# M3_Chip.net
KiCad netlist of a schematic drawn in Altium Designer
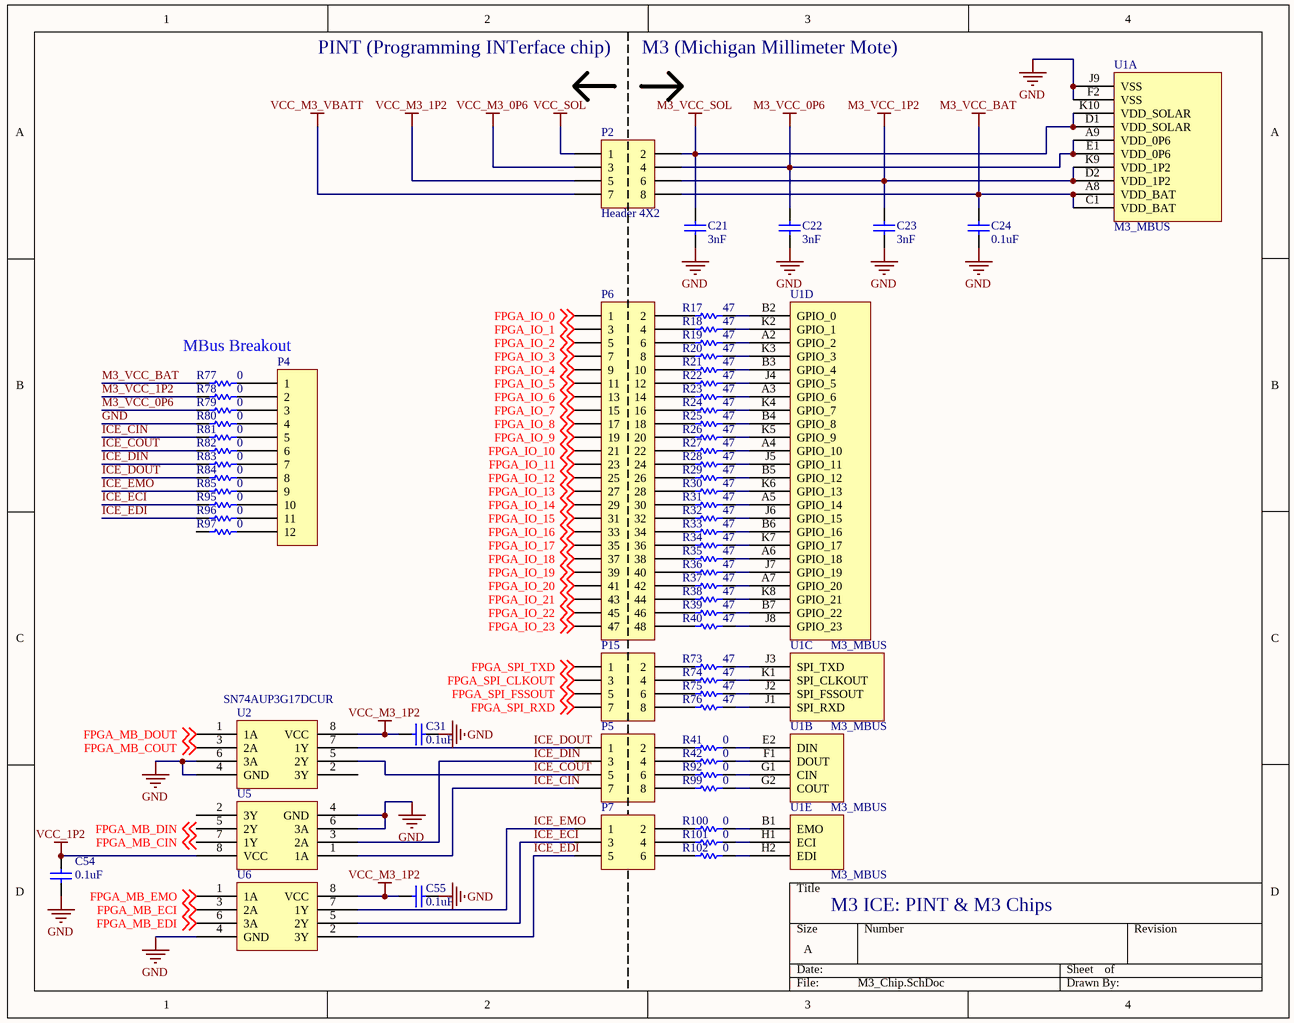
[diagram p0: M3_Chip.SchDoc]

(export (version "E")
  (design (tool "Eeschema 10.0.6"))
  (components
    (comp (ref "C21")
      (value "3nF")
      (footprint "1608[0603]")
      (description "Capacitor (Semiconductor SIM Model)")
      (fields
        (field (name "DISTPARTNO") "399-7893-1-ND")
        (field (name "MANPARTNO") "C0603C302K5GACTU")
        (field (name "PUBLISHER") "Altium Limited")
      )
      (libsource (lib "Miscellaneous Devices") (part "Cap Semi"))
    )
    (comp (ref "C22")
      (value "3nF")
      (footprint "1608[0603]")
      (description "Capacitor (Semiconductor SIM Model)")
      (fields
        (field (name "DISTPARTNO") "399-7893-1-ND")
        (field (name "MANPARTNO") "C0603C302K5GACTU")
        (field (name "PUBLISHER") "Altium Limited")
      )
      (libsource (lib "Miscellaneous Devices") (part "Cap Semi"))
    )
    (comp (ref "C23")
      (value "3nF")
      (footprint "1608[0603]")
      (description "Capacitor (Semiconductor SIM Model)")
      (fields
        (field (name "DISTPARTNO") "399-7893-1-ND")
        (field (name "MANPARTNO") "C0603C302K5GACTU")
        (field (name "PUBLISHER") "Altium Limited")
      )
      (libsource (lib "Miscellaneous Devices") (part "Cap Semi"))
    )
    (comp (ref "C24")
      (value "0.1uF")
      (footprint "1608[0603]")
      (description "Capacitor (Semiconductor SIM Model)")
      (fields
        (field (name "DISTPARTNO") "1276-1005-1-ND")
        (field (name "MANPARTNO") "CL10B104KO8NNNC")
        (field (name "PUBLISHER") "Altium Limited")
      )
      (libsource (lib "Miscellaneous Devices") (part "Cap Semi"))
    )
    (comp (ref "C31")
      (value "0.1uF")
      (footprint "1608[0603]")
      (description "Capacitor (Semiconductor SIM Model)")
      (fields
        (field (name "DISTPARTNO") "1276-1005-1-ND")
        (field (name "MANPARTNO") "CL10B104KO8NNNC")
        (field (name "PUBLISHER") "Altium Limited")
      )
      (libsource (lib "Miscellaneous Devices") (part "Cap Semi"))
    )
    (comp (ref "C54")
      (value "0.1uF")
      (footprint "1608[0603]")
      (description "Capacitor (Semiconductor SIM Model)")
      (fields
        (field (name "DISTPARTNO") "1276-1005-1-ND")
        (field (name "MANPARTNO") "CL10B104KO8NNNC")
        (field (name "PUBLISHER") "Altium Limited")
      )
      (libsource (lib "Miscellaneous Devices") (part "Cap Semi"))
    )
    (comp (ref "C55")
      (value "0.1uF")
      (footprint "1608[0603]")
      (description "Capacitor (Semiconductor SIM Model)")
      (fields
        (field (name "DISTPARTNO") "1276-1005-1-ND")
        (field (name "MANPARTNO") "CL10B104KO8NNNC")
        (field (name "PUBLISHER") "Altium Limited")
      )
      (libsource (lib "Miscellaneous Devices") (part "Cap Semi"))
    )
    (comp (ref "P2")
      (value "Header 4X2")
      (footprint "HDR2X4")
      (description "Header, 4-Pin, Dual row")
      (fields
        (field (name "DISTPARTNO") "A26530-04-ND")
        (field (name "MANPARTNO") "4-103328-0-04")
        (field (name "PUBLISHER") "Altium Limited")
      )
      (libsource (lib "Miscellaneous Connectors") (part "Header 4X2"))
    )
    (comp (ref "P4")
      (value "MBus Breakout")
      (footprint "HDR1X12")
      (description "Header, 12-Pin")
      (fields
        (field (name "DISTPARTNO") "A26514-12-ND")
        (field (name "MANPARTNO") "4-103327-0-12")
        (field (name "PUBLISHER") "Altium Limited")
      )
      (libsource (lib "Miscellaneous Connectors") (part "Header 12"))
    )
    (comp (ref "P5")
      (value "Header 4X2")
      (footprint "HDR2X4")
      (description "Header, 4-Pin, Dual row")
      (fields
        (field (name "MANPARTNO") "4-103328-0-04")
        (field (name "DISTPARTNO") "A26530-04-ND")
        (field (name "PUBLISHER") "Altium Limited")
      )
      (libsource (lib "Miscellaneous Connectors") (part "Header 4X2"))
    )
    (comp (ref "P6")
      (value "Header 24X2")
      (footprint "HDR2X24")
      (description "Header, 24-Pin, Dual row")
      (fields
        (field (name "MANPARTNO") "4-103328-0-24")
        (field (name "DISTPARTNO") "A26530-24-ND")
        (field (name "PUBLISHER") "Altium Limited")
      )
      (libsource (lib "Miscellaneous Connectors") (part "Header 24X2"))
    )
    (comp (ref "P7")
      (value "Header 3X2")
      (footprint "HDR2X3")
      (description "Header, 3-Pin, Dual row")
      (fields
        (field (name "DISTPARTNO") "A26525-03-ND")
        (field (name "MANPARTNO") "4-103777-0-03")
        (field (name "PUBLISHER") "Altium Limited")
      )
      (libsource (lib "Miscellaneous Connectors") (part "Header 3X2"))
    )
    (comp (ref "P15")
      (value "Header 4X2")
      (footprint "HDR2X4")
      (description "Header, 4-Pin, Dual row")
      (fields
        (field (name "MANPARTNO") "4-103328-0-04")
        (field (name "DISTPARTNO") "A26530-04-ND")
        (field (name "PUBLISHER") "Altium Limited")
      )
      (libsource (lib "Miscellaneous Connectors") (part "Header 4X2"))
    )
    (comp (ref "R17")
      (value "47")
      (footprint "0603")
      (description "Semiconductor Resistor")
      (fields
        (field (name "DISTPARTNO") "P47GCT-ND")
        (field (name "MANPARTNO") "ERJ-3GEYJ470V")
        (field (name "PUBLISHER") "Altium Limited")
      )
      (libsource (lib "M3") (part "Res Chip"))
    )
    (comp (ref "R18")
      (value "47")
      (footprint "0603")
      (description "Semiconductor Resistor")
      (fields
        (field (name "DISTPARTNO") "P47GCT-ND")
        (field (name "MANPARTNO") "ERJ-3GEYJ470V")
        (field (name "PUBLISHER") "Altium Limited")
      )
      (libsource (lib "M3") (part "Res Chip"))
    )
    (comp (ref "R19")
      (value "47")
      (footprint "0603")
      (description "Semiconductor Resistor")
      (fields
        (field (name "DISTPARTNO") "P47GCT-ND")
        (field (name "MANPARTNO") "ERJ-3GEYJ470V")
        (field (name "PUBLISHER") "Altium Limited")
      )
      (libsource (lib "M3") (part "Res Chip"))
    )
    (comp (ref "R20")
      (value "47")
      (footprint "0603")
      (description "Semiconductor Resistor")
      (fields
        (field (name "DISTPARTNO") "P47GCT-ND")
        (field (name "MANPARTNO") "ERJ-3GEYJ470V")
        (field (name "PUBLISHER") "Altium Limited")
      )
      (libsource (lib "M3") (part "Res Chip"))
    )
    (comp (ref "R21")
      (value "47")
      (footprint "0603")
      (description "Semiconductor Resistor")
      (fields
        (field (name "DISTPARTNO") "P47GCT-ND")
        (field (name "MANPARTNO") "ERJ-3GEYJ470V")
        (field (name "PUBLISHER") "Altium Limited")
      )
      (libsource (lib "M3") (part "Res Chip"))
    )
    (comp (ref "R22")
      (value "47")
      (footprint "0603")
      (description "Semiconductor Resistor")
      (fields
        (field (name "DISTPARTNO") "P47GCT-ND")
        (field (name "MANPARTNO") "ERJ-3GEYJ470V")
        (field (name "PUBLISHER") "Altium Limited")
      )
      (libsource (lib "M3") (part "Res Chip"))
    )
    (comp (ref "R23")
      (value "47")
      (footprint "0603")
      (description "Semiconductor Resistor")
      (fields
        (field (name "DISTPARTNO") "P47GCT-ND")
        (field (name "MANPARTNO") "ERJ-3GEYJ470V")
        (field (name "PUBLISHER") "Altium Limited")
      )
      (libsource (lib "M3") (part "Res Chip"))
    )
    (comp (ref "R24")
      (value "47")
      (footprint "0603")
      (description "Semiconductor Resistor")
      (fields
        (field (name "DISTPARTNO") "P47GCT-ND")
        (field (name "MANPARTNO") "ERJ-3GEYJ470V")
        (field (name "PUBLISHER") "Altium Limited")
      )
      (libsource (lib "M3") (part "Res Chip"))
    )
    (comp (ref "R25")
      (value "47")
      (footprint "0603")
      (description "Semiconductor Resistor")
      (fields
        (field (name "DISTPARTNO") "P47GCT-ND")
        (field (name "MANPARTNO") "ERJ-3GEYJ470V")
        (field (name "PUBLISHER") "Altium Limited")
      )
      (libsource (lib "M3") (part "Res Chip"))
    )
    (comp (ref "R26")
      (value "47")
      (footprint "0603")
      (description "Semiconductor Resistor")
      (fields
        (field (name "DISTPARTNO") "P47GCT-ND")
        (field (name "MANPARTNO") "ERJ-3GEYJ470V")
        (field (name "PUBLISHER") "Altium Limited")
      )
      (libsource (lib "M3") (part "Res Chip"))
    )
    (comp (ref "R27")
      (value "47")
      (footprint "0603")
      (description "Semiconductor Resistor")
      (fields
        (field (name "DISTPARTNO") "P47GCT-ND")
        (field (name "MANPARTNO") "ERJ-3GEYJ470V")
        (field (name "PUBLISHER") "Altium Limited")
      )
      (libsource (lib "M3") (part "Res Chip"))
    )
    (comp (ref "R28")
      (value "47")
      (footprint "0603")
      (description "Semiconductor Resistor")
      (fields
        (field (name "DISTPARTNO") "P47GCT-ND")
        (field (name "MANPARTNO") "ERJ-3GEYJ470V")
        (field (name "PUBLISHER") "Altium Limited")
      )
      (libsource (lib "M3") (part "Res Chip"))
    )
    (comp (ref "R29")
      (value "47")
      (footprint "0603")
      (description "Semiconductor Resistor")
      (fields
        (field (name "DISTPARTNO") "P47GCT-ND")
        (field (name "MANPARTNO") "ERJ-3GEYJ470V")
        (field (name "PUBLISHER") "Altium Limited")
      )
      (libsource (lib "M3") (part "Res Chip"))
    )
    (comp (ref "R30")
      (value "47")
      (footprint "0603")
      (description "Semiconductor Resistor")
      (fields
        (field (name "DISTPARTNO") "P47GCT-ND")
        (field (name "MANPARTNO") "ERJ-3GEYJ470V")
        (field (name "PUBLISHER") "Altium Limited")
      )
      (libsource (lib "M3") (part "Res Chip"))
    )
    (comp (ref "R31")
      (value "47")
      (footprint "0603")
      (description "Semiconductor Resistor")
      (fields
        (field (name "DISTPARTNO") "P47GCT-ND")
        (field (name "MANPARTNO") "ERJ-3GEYJ470V")
        (field (name "PUBLISHER") "Altium Limited")
      )
      (libsource (lib "M3") (part "Res Chip"))
    )
    (comp (ref "R32")
      (value "47")
      (footprint "0603")
      (description "Semiconductor Resistor")
      (fields
        (field (name "DISTPARTNO") "P47GCT-ND")
        (field (name "MANPARTNO") "ERJ-3GEYJ470V")
        (field (name "PUBLISHER") "Altium Limited")
      )
      (libsource (lib "M3") (part "Res Chip"))
    )
    (comp (ref "R33")
      (value "47")
      (footprint "0603")
      (description "Semiconductor Resistor")
      (fields
        (field (name "DISTPARTNO") "P47GCT-ND")
        (field (name "MANPARTNO") "ERJ-3GEYJ470V")
        (field (name "PUBLISHER") "Altium Limited")
      )
      (libsource (lib "M3") (part "Res Chip"))
    )
    (comp (ref "R34")
      (value "47")
      (footprint "0603")
      (description "Semiconductor Resistor")
      (fields
        (field (name "DISTPARTNO") "P47GCT-ND")
        (field (name "MANPARTNO") "ERJ-3GEYJ470V")
        (field (name "PUBLISHER") "Altium Limited")
      )
      (libsource (lib "M3") (part "Res Chip"))
    )
    (comp (ref "R35")
      (value "47")
      (footprint "0603")
      (description "Semiconductor Resistor")
      (fields
        (field (name "DISTPARTNO") "P47GCT-ND")
        (field (name "MANPARTNO") "ERJ-3GEYJ470V")
        (field (name "PUBLISHER") "Altium Limited")
      )
      (libsource (lib "M3") (part "Res Chip"))
    )
    (comp (ref "R36")
      (value "47")
      (footprint "0603")
      (description "Semiconductor Resistor")
      (fields
        (field (name "DISTPARTNO") "P47GCT-ND")
        (field (name "MANPARTNO") "ERJ-3GEYJ470V")
        (field (name "PUBLISHER") "Altium Limited")
      )
      (libsource (lib "M3") (part "Res Chip"))
    )
    (comp (ref "R37")
      (value "47")
      (footprint "0603")
      (description "Semiconductor Resistor")
      (fields
        (field (name "DISTPARTNO") "P47GCT-ND")
        (field (name "MANPARTNO") "ERJ-3GEYJ470V")
        (field (name "PUBLISHER") "Altium Limited")
      )
      (libsource (lib "M3") (part "Res Chip"))
    )
    (comp (ref "R38")
      (value "47")
      (footprint "0603")
      (description "Semiconductor Resistor")
      (fields
        (field (name "DISTPARTNO") "P47GCT-ND")
        (field (name "MANPARTNO") "ERJ-3GEYJ470V")
        (field (name "PUBLISHER") "Altium Limited")
      )
      (libsource (lib "M3") (part "Res Chip"))
    )
    (comp (ref "R39")
      (value "47")
      (footprint "0603")
      (description "Semiconductor Resistor")
      (fields
        (field (name "DISTPARTNO") "P47GCT-ND")
        (field (name "MANPARTNO") "ERJ-3GEYJ470V")
        (field (name "PUBLISHER") "Altium Limited")
      )
      (libsource (lib "M3") (part "Res Chip"))
    )
    (comp (ref "R40")
      (value "47")
      (footprint "0603")
      (description "Semiconductor Resistor")
      (fields
        (field (name "DISTPARTNO") "P47GCT-ND")
        (field (name "MANPARTNO") "ERJ-3GEYJ470V")
        (field (name "PUBLISHER") "Altium Limited")
      )
      (libsource (lib "M3") (part "Res Chip"))
    )
    (comp (ref "R41")
      (value "0")
      (footprint "0603")
      (description "Semiconductor Resistor")
      (fields
        (field (name "DISTPARTNO") "P0.0GCT-ND")
        (field (name "MANPARTNO") "ERJ-3GEY0R00V")
        (field (name "PUBLISHER") "Altium Limited")
      )
      (libsource (lib "M3") (part "Res Chip"))
    )
    (comp (ref "R42")
      (value "0")
      (footprint "0603")
      (description "Semiconductor Resistor")
      (fields
        (field (name "DISTPARTNO") "P0.0GCT-ND")
        (field (name "MANPARTNO") "ERJ-3GEY0R00V")
        (field (name "PUBLISHER") "Altium Limited")
      )
      (libsource (lib "M3") (part "Res Chip"))
    )
    (comp (ref "R73")
      (value "47")
      (footprint "0603")
      (description "Semiconductor Resistor")
      (fields
        (field (name "DISTPARTNO") "P47GCT-ND")
        (field (name "MANPARTNO") "ERJ-3GEYJ470V")
        (field (name "PUBLISHER") "Altium Limited")
      )
      (libsource (lib "M3") (part "Res Chip"))
    )
    (comp (ref "R74")
      (value "47")
      (footprint "0603")
      (description "Semiconductor Resistor")
      (fields
        (field (name "DISTPARTNO") "P47GCT-ND")
        (field (name "MANPARTNO") "ERJ-3GEYJ470V")
        (field (name "PUBLISHER") "Altium Limited")
      )
      (libsource (lib "M3") (part "Res Chip"))
    )
    (comp (ref "R75")
      (value "47")
      (footprint "0603")
      (description "Semiconductor Resistor")
      (fields
        (field (name "DISTPARTNO") "P47GCT-ND")
        (field (name "MANPARTNO") "ERJ-3GEYJ470V")
        (field (name "PUBLISHER") "Altium Limited")
      )
      (libsource (lib "M3") (part "Res Chip"))
    )
    (comp (ref "R76")
      (value "47")
      (footprint "0603")
      (description "Semiconductor Resistor")
      (fields
        (field (name "DISTPARTNO") "P47GCT-ND")
        (field (name "MANPARTNO") "ERJ-3GEYJ470V")
        (field (name "PUBLISHER") "Altium Limited")
      )
      (libsource (lib "M3") (part "Res Chip"))
    )
    (comp (ref "R77")
      (value "0")
      (footprint "0603")
      (description "Semiconductor Resistor")
      (fields
        (field (name "DISTPARTNO") "P0.0GCT-ND")
        (field (name "MANPARTNO") "ERJ-3GEY0R00V")
        (field (name "PUBLISHER") "Altium Limited")
      )
      (libsource (lib "M3") (part "Res Chip"))
    )
    (comp (ref "R78")
      (value "0")
      (footprint "0603")
      (description "Semiconductor Resistor")
      (fields
        (field (name "DISTPARTNO") "P0.0GCT-ND")
        (field (name "MANPARTNO") "ERJ-3GEY0R00V")
        (field (name "PUBLISHER") "Altium Limited")
      )
      (libsource (lib "M3") (part "Res Chip"))
    )
    (comp (ref "R79")
      (value "0")
      (footprint "0603")
      (description "Semiconductor Resistor")
      (fields
        (field (name "DISTPARTNO") "P0.0GCT-ND")
        (field (name "MANPARTNO") "ERJ-3GEY0R00V")
        (field (name "PUBLISHER") "Altium Limited")
      )
      (libsource (lib "M3") (part "Res Chip"))
    )
    (comp (ref "R80")
      (value "0")
      (footprint "0603")
      (description "Semiconductor Resistor")
      (fields
        (field (name "DISTPARTNO") "P0.0GCT-ND")
        (field (name "MANPARTNO") "ERJ-3GEY0R00V")
        (field (name "PUBLISHER") "Altium Limited")
      )
      (libsource (lib "M3") (part "Res Chip"))
    )
    (comp (ref "R81")
      (value "0")
      (footprint "0603")
      (description "Semiconductor Resistor")
      (fields
        (field (name "DISTPARTNO") "P0.0GCT-ND")
        (field (name "MANPARTNO") "ERJ-3GEY0R00V")
        (field (name "PUBLISHER") "Altium Limited")
      )
      (libsource (lib "M3") (part "Res Chip"))
    )
    (comp (ref "R82")
      (value "0")
      (footprint "0603")
      (description "Semiconductor Resistor")
      (fields
        (field (name "DISTPARTNO") "P0.0GCT-ND")
        (field (name "MANPARTNO") "ERJ-3GEY0R00V")
        (field (name "PUBLISHER") "Altium Limited")
      )
      (libsource (lib "M3") (part "Res Chip"))
    )
    (comp (ref "R83")
      (value "0")
      (footprint "0603")
      (description "Semiconductor Resistor")
      (fields
        (field (name "DISTPARTNO") "P0.0GCT-ND")
        (field (name "MANPARTNO") "ERJ-3GEY0R00V")
        (field (name "PUBLISHER") "Altium Limited")
      )
      (libsource (lib "M3") (part "Res Chip"))
    )
    (comp (ref "R84")
      (value "0")
      (footprint "0603")
      (description "Semiconductor Resistor")
      (fields
        (field (name "DISTPARTNO") "P0.0GCT-ND")
        (field (name "MANPARTNO") "ERJ-3GEY0R00V")
        (field (name "PUBLISHER") "Altium Limited")
      )
      (libsource (lib "M3") (part "Res Chip"))
    )
    (comp (ref "R85")
      (value "0")
      (footprint "0603")
      (description "Semiconductor Resistor")
      (fields
        (field (name "DISTPARTNO") "P0.0GCT-ND")
        (field (name "MANPARTNO") "ERJ-3GEY0R00V")
        (field (name "PUBLISHER") "Altium Limited")
      )
      (libsource (lib "M3") (part "Res Chip"))
    )
    (comp (ref "R92")
      (value "0")
      (footprint "0603")
      (description "Semiconductor Resistor")
      (fields
        (field (name "DISTPARTNO") "P0.0GCT-ND")
        (field (name "MANPARTNO") "ERJ-3GEY0R00V")
        (field (name "PUBLISHER") "Altium Limited")
      )
      (libsource (lib "M3") (part "Res Chip"))
    )
    (comp (ref "R95")
      (value "0")
      (footprint "0603")
      (description "Semiconductor Resistor")
      (fields
        (field (name "DISTPARTNO") "P0.0GCT-ND")
        (field (name "MANPARTNO") "ERJ-3GEY0R00V")
        (field (name "PUBLISHER") "Altium Limited")
      )
      (libsource (lib "M3") (part "Res Chip"))
    )
    (comp (ref "R96")
      (value "0")
      (footprint "0603")
      (description "Semiconductor Resistor")
      (fields
        (field (name "DISTPARTNO") "P0.0GCT-ND")
        (field (name "MANPARTNO") "ERJ-3GEY0R00V")
        (field (name "PUBLISHER") "Altium Limited")
      )
      (libsource (lib "M3") (part "Res Chip"))
    )
    (comp (ref "R97")
      (value "0")
      (footprint "0603")
      (description "Semiconductor Resistor")
      (fields
        (field (name "DISTPARTNO") "P0.0GCT-ND")
        (field (name "MANPARTNO") "ERJ-3GEY0R00V")
        (field (name "PUBLISHER") "Altium Limited")
      )
      (libsource (lib "M3") (part "Res Chip"))
    )
    (comp (ref "R99")
      (value "0")
      (footprint "0603")
      (description "Semiconductor Resistor")
      (fields
        (field (name "DISTPARTNO") "P0.0GCT-ND")
        (field (name "MANPARTNO") "ERJ-3GEY0R00V")
        (field (name "PUBLISHER") "Altium Limited")
      )
      (libsource (lib "M3") (part "Res Chip"))
    )
    (comp (ref "R100")
      (value "0")
      (footprint "0603")
      (description "Semiconductor Resistor")
      (fields
        (field (name "DISTPARTNO") "P0.0GCT-ND")
        (field (name "MANPARTNO") "ERJ-3GEY0R00V")
        (field (name "PUBLISHER") "Altium Limited")
      )
      (libsource (lib "M3") (part "Res Chip"))
    )
    (comp (ref "R101")
      (value "0")
      (footprint "0603")
      (description "Semiconductor Resistor")
      (fields
        (field (name "DISTPARTNO") "P0.0GCT-ND")
        (field (name "MANPARTNO") "ERJ-3GEY0R00V")
        (field (name "PUBLISHER") "Altium Limited")
      )
      (libsource (lib "M3") (part "Res Chip"))
    )
    (comp (ref "R102")
      (value "0")
      (footprint "0603")
      (description "Semiconductor Resistor")
      (fields
        (field (name "DISTPARTNO") "P0.0GCT-ND")
        (field (name "MANPARTNO") "ERJ-3GEY0R00V")
        (field (name "PUBLISHER") "Altium Limited")
      )
      (libsource (lib "M3") (part "Res Chip"))
    )
    (comp (ref "U1")
      (value "M3_MBUS")
      (footprint "CPGA-65")
      (fields (field (name "DISTPARTNO") "3M5066-ND") (field (name "MANPARTNO") "200-6310-9UN-1900"))
      (libsource (lib "M3") (part "M3_MBUS"))
    )
    (comp (ref "U2")
      (value "SN74AUP3G17DCUR")
      (footprint "VFSOP-8")
      (fields (field (name "DISTPARTNO") "296-25596-1-ND"))
      (libsource (lib "M3") (part "SN74AUP3G17DCUR"))
    )
    (comp (ref "U5")
      (value "SN74AUP3G17DCUR")
      (footprint "VFSOP-8")
      (fields (field (name "DISTPARTNO") "296-25596-1-ND"))
      (libsource (lib "") (part "SN74AUP3G17DCUR_1"))
    )
    (comp (ref "U6")
      (value "SN74AUP3G17DCUR")
      (footprint "VFSOP-8")
      (fields (field (name "DISTPARTNO") "296-25596-1-ND"))
      (libsource (lib "M3") (part "SN74AUP3G17DCUR"))
    )
  )
  (nets
    (net (code "1") (name "/ICE_CIN") (class "Default")
      (node (ref "P5") (pin "7") (pinfunction "7_7") (pintype "passive"))
      (node (ref "R81") (pin "2") (pinfunction "2_2") (pintype "passive"))
      (node (ref "U5") (pin "1") (pinfunction "1A_1") (pintype "passive"))
    )
    (net (code "2") (name "/ICE_COUT") (class "Default")
      (node (ref "P5") (pin "5") (pinfunction "5_5") (pintype "passive"))
      (node (ref "R82") (pin "2") (pinfunction "2_2") (pintype "passive"))
      (node (ref "U2") (pin "5") (pinfunction "2Y_5") (pintype "passive"))
    )
    (net (code "3") (name "/ICE_DIN") (class "Default")
      (node (ref "P5") (pin "3") (pinfunction "3_3") (pintype "passive"))
      (node (ref "R83") (pin "2") (pinfunction "2_2") (pintype "passive"))
      (node (ref "U5") (pin "3") (pinfunction "2A_3") (pintype "passive"))
    )
    (net (code "4") (name "/ICE_DOUT") (class "Default")
      (node (ref "P5") (pin "1") (pinfunction "1_1") (pintype "passive"))
      (node (ref "R84") (pin "2") (pinfunction "2_2") (pintype "passive"))
      (node (ref "U2") (pin "7") (pinfunction "1Y_7") (pintype "passive"))
    )
    (net (code "5") (name "/ICE_ECI") (class "Default")
      (node (ref "P7") (pin "3") (pinfunction "3_3") (pintype "passive"))
      (node (ref "R95") (pin "2") (pinfunction "2_2") (pintype "passive"))
      (node (ref "U6") (pin "5") (pinfunction "2Y_5") (pintype "passive"))
    )
    (net (code "6") (name "/ICE_EDI") (class "Default")
      (node (ref "P7") (pin "5") (pinfunction "5_5") (pintype "passive"))
      (node (ref "R96") (pin "2") (pinfunction "2_2") (pintype "passive"))
      (node (ref "U6") (pin "2") (pinfunction "3Y_2") (pintype "passive"))
    )
    (net (code "7") (name "/ICE_EMO") (class "Default")
      (node (ref "P7") (pin "1") (pinfunction "1_1") (pintype "passive"))
      (node (ref "R85") (pin "2") (pinfunction "2_2") (pintype "passive"))
      (node (ref "U6") (pin "7") (pinfunction "1Y_7") (pintype "passive"))
    )
    (net (code "8") (name "FPGA_IO_0") (class "Default")
      (node (ref "P6") (pin "1") (pinfunction "1_1") (pintype "passive"))
    )
    (net (code "9") (name "FPGA_IO_1") (class "Default")
      (node (ref "P6") (pin "3") (pinfunction "3_3") (pintype "passive"))
    )
    (net (code "10") (name "FPGA_IO_2") (class "Default")
      (node (ref "P6") (pin "5") (pinfunction "5_5") (pintype "passive"))
    )
    (net (code "11") (name "FPGA_IO_3") (class "Default")
      (node (ref "P6") (pin "7") (pinfunction "7_7") (pintype "passive"))
    )
    (net (code "12") (name "FPGA_IO_4") (class "Default")
      (node (ref "P6") (pin "9") (pinfunction "9_9") (pintype "passive"))
    )
    (net (code "13") (name "FPGA_IO_5") (class "Default")
      (node (ref "P6") (pin "11") (pinfunction "11_11") (pintype "passive"))
    )
    (net (code "14") (name "FPGA_IO_6") (class "Default")
      (node (ref "P6") (pin "13") (pinfunction "13_13") (pintype "passive"))
    )
    (net (code "15") (name "FPGA_IO_7") (class "Default")
      (node (ref "P6") (pin "15") (pinfunction "15_15") (pintype "passive"))
    )
    (net (code "16") (name "FPGA_IO_8") (class "Default")
      (node (ref "P6") (pin "17") (pinfunction "17_17") (pintype "passive"))
    )
    (net (code "17") (name "FPGA_IO_9") (class "Default")
      (node (ref "P6") (pin "19") (pinfunction "19_19") (pintype "passive"))
    )
    (net (code "18") (name "FPGA_IO_10") (class "Default")
      (node (ref "P6") (pin "21") (pinfunction "21_21") (pintype "passive"))
    )
    (net (code "19") (name "FPGA_IO_11") (class "Default")
      (node (ref "P6") (pin "23") (pinfunction "23_23") (pintype "passive"))
    )
    (net (code "20") (name "FPGA_IO_12") (class "Default")
      (node (ref "P6") (pin "25") (pinfunction "25_25") (pintype "passive"))
    )
    (net (code "21") (name "FPGA_IO_13") (class "Default")
      (node (ref "P6") (pin "27") (pinfunction "27_27") (pintype "passive"))
    )
    (net (code "22") (name "FPGA_IO_14") (class "Default")
      (node (ref "P6") (pin "29") (pinfunction "29_29") (pintype "passive"))
    )
    (net (code "23") (name "FPGA_IO_15") (class "Default")
      (node (ref "P6") (pin "31") (pinfunction "31_31") (pintype "passive"))
    )
    (net (code "24") (name "FPGA_IO_16") (class "Default")
      (node (ref "P6") (pin "33") (pinfunction "33_33") (pintype "passive"))
    )
    (net (code "25") (name "FPGA_IO_17") (class "Default")
      (node (ref "P6") (pin "35") (pinfunction "35_35") (pintype "passive"))
    )
    (net (code "26") (name "FPGA_IO_18") (class "Default")
      (node (ref "P6") (pin "37") (pinfunction "37_37") (pintype "passive"))
    )
    (net (code "27") (name "FPGA_IO_19") (class "Default")
      (node (ref "P6") (pin "39") (pinfunction "39_39") (pintype "passive"))
    )
    (net (code "28") (name "FPGA_IO_20") (class "Default")
      (node (ref "P6") (pin "41") (pinfunction "41_41") (pintype "passive"))
    )
    (net (code "29") (name "FPGA_IO_21") (class "Default")
      (node (ref "P6") (pin "43") (pinfunction "43_43") (pintype "passive"))
    )
    (net (code "30") (name "FPGA_IO_22") (class "Default")
      (node (ref "P6") (pin "45") (pinfunction "45_45") (pintype "passive"))
    )
    (net (code "31") (name "FPGA_IO_23") (class "Default")
      (node (ref "P6") (pin "47") (pinfunction "47_47") (pintype "passive"))
    )
    (net (code "32") (name "FPGA_MB_CIN") (class "Default")
      (node (ref "U5") (pin "7") (pinfunction "1Y_7") (pintype "passive"))
    )
    (net (code "33") (name "FPGA_MB_COUT") (class "Default")
      (node (ref "U2") (pin "3") (pinfunction "2A_3") (pintype "passive"))
    )
    (net (code "34") (name "FPGA_MB_DIN") (class "Default")
      (node (ref "U5") (pin "5") (pinfunction "2Y_5") (pintype "passive"))
    )
    (net (code "35") (name "FPGA_MB_DOUT") (class "Default")
      (node (ref "U2") (pin "1") (pinfunction "1A_1") (pintype "passive"))
    )
    (net (code "36") (name "FPGA_MB_ECI") (class "Default")
      (node (ref "U6") (pin "3") (pinfunction "2A_3") (pintype "passive"))
    )
    (net (code "37") (name "FPGA_MB_EDI") (class "Default")
      (node (ref "U6") (pin "6") (pinfunction "3A_6") (pintype "passive"))
    )
    (net (code "38") (name "FPGA_MB_EMO") (class "Default")
      (node (ref "U6") (pin "1") (pinfunction "1A_1") (pintype "passive"))
    )
    (net (code "39") (name "FPGA_SPI_CLKOUT") (class "Default")
      (node (ref "P15") (pin "3") (pinfunction "3_3") (pintype "passive"))
    )
    (net (code "40") (name "FPGA_SPI_FSSOUT") (class "Default")
      (node (ref "P15") (pin "5") (pinfunction "5_5") (pintype "passive"))
    )
    (net (code "41") (name "FPGA_SPI_RXD") (class "Default")
      (node (ref "P15") (pin "7") (pinfunction "7_7") (pintype "passive"))
    )
    (net (code "42") (name "FPGA_SPI_TXD") (class "Default")
      (node (ref "P15") (pin "1") (pinfunction "1_1") (pintype "passive"))
    )
    (net (code "43") (name "GND") (class "Default")
      (node (ref "C21") (pin "1") (pinfunction "1_1") (pintype "passive"))
      (node (ref "C22") (pin "1") (pinfunction "1_1") (pintype "passive"))
      (node (ref "C23") (pin "1") (pinfunction "1_1") (pintype "passive"))
      (node (ref "C24") (pin "1") (pinfunction "1_1") (pintype "passive"))
      (node (ref "C31") (pin "1") (pinfunction "1_1") (pintype "passive"))
      (node (ref "C54") (pin "1") (pinfunction "1_1") (pintype "passive"))
      (node (ref "C55") (pin "1") (pinfunction "1_1") (pintype "passive"))
      (node (ref "R80") (pin "2") (pinfunction "2_2") (pintype "passive"))
      (node (ref "U1") (pin "F2") (pinfunction "VSS_F2") (pintype "passive"))
      (node (ref "U1") (pin "J9") (pinfunction "VSS_J9") (pintype "passive"))
      (node (ref "U2") (pin "4") (pinfunction "GND_4") (pintype "passive"))
      (node (ref "U2") (pin "6") (pinfunction "3A_6") (pintype "passive"))
      (node (ref "U5") (pin "4") (pinfunction "GND_4") (pintype "passive"))
      (node (ref "U5") (pin "6") (pinfunction "3A_6") (pintype "passive"))
      (node (ref "U6") (pin "4") (pinfunction "GND_4") (pintype "passive"))
    )
    (net (code "44") (name "M3_VCC_0P6") (class "Default")
      (node (ref "C22") (pin "2") (pinfunction "2_2") (pintype "passive"))
      (node (ref "P2") (pin "4") (pinfunction "4_4") (pintype "passive"))
      (node (ref "R79") (pin "2") (pinfunction "2_2") (pintype "passive"))
      (node (ref "U1") (pin "A9") (pinfunction "VDD_0P6_A9") (pintype "passive"))
      (node (ref "U1") (pin "E1") (pinfunction "VDD_0P6_E1") (pintype "passive"))
    )
    (net (code "45") (name "M3_VCC_1P2") (class "Default")
      (node (ref "C23") (pin "2") (pinfunction "2_2") (pintype "passive"))
      (node (ref "P2") (pin "6") (pinfunction "6_6") (pintype "passive"))
      (node (ref "R78") (pin "2") (pinfunction "2_2") (pintype "passive"))
      (node (ref "U1") (pin "D2") (pinfunction "VDD_1P2_D2") (pintype "passive"))
      (node (ref "U1") (pin "K9") (pinfunction "VDD_1P2_K9") (pintype "passive"))
    )
    (net (code "46") (name "M3_VCC_BAT") (class "Default")
      (node (ref "C24") (pin "2") (pinfunction "2_2") (pintype "passive"))
      (node (ref "P2") (pin "8") (pinfunction "8_8") (pintype "passive"))
      (node (ref "R77") (pin "2") (pinfunction "2_2") (pintype "passive"))
      (node (ref "U1") (pin "A8") (pinfunction "VDD_BAT_A8") (pintype "passive"))
      (node (ref "U1") (pin "C1") (pinfunction "VDD_BAT_C1") (pintype "passive"))
    )
    (net (code "47") (name "M3_VCC_SOL") (class "Default")
      (node (ref "C21") (pin "2") (pinfunction "2_2") (pintype "passive"))
      (node (ref "P2") (pin "2") (pinfunction "2_2") (pintype "passive"))
      (node (ref "U1") (pin "D1") (pinfunction "VDD_SOLAR_D1") (pintype "passive"))
      (node (ref "U1") (pin "K10") (pinfunction "VDD_SOLAR_K10") (pintype "passive"))
    )
    (net (code "48") (name "Net-(P4-Pad1)") (class "Default")
      (node (ref "P4") (pin "1") (pinfunction "1_1") (pintype "passive"))
      (node (ref "R77") (pin "1") (pinfunction "1_1") (pintype "passive"))
    )
    (net (code "49") (name "Net-(P4-Pad2)") (class "Default")
      (node (ref "P4") (pin "2") (pinfunction "2_2") (pintype "passive"))
      (node (ref "R78") (pin "1") (pinfunction "1_1") (pintype "passive"))
    )
    (net (code "50") (name "Net-(P4-Pad3)") (class "Default")
      (node (ref "P4") (pin "3") (pinfunction "3_3") (pintype "passive"))
      (node (ref "R79") (pin "1") (pinfunction "1_1") (pintype "passive"))
    )
    (net (code "51") (name "Net-(P4-Pad4)") (class "Default")
      (node (ref "P4") (pin "4") (pinfunction "4_4") (pintype "passive"))
      (node (ref "R80") (pin "1") (pinfunction "1_1") (pintype "passive"))
    )
    (net (code "52") (name "Net-(P4-Pad5)") (class "Default")
      (node (ref "P4") (pin "5") (pinfunction "5_5") (pintype "passive"))
      (node (ref "R81") (pin "1") (pinfunction "1_1") (pintype "passive"))
    )
    (net (code "53") (name "Net-(P4-Pad6)") (class "Default")
      (node (ref "P4") (pin "6") (pinfunction "6_6") (pintype "passive"))
      (node (ref "R82") (pin "1") (pinfunction "1_1") (pintype "passive"))
    )
    (net (code "54") (name "Net-(P4-Pad7)") (class "Default")
      (node (ref "P4") (pin "7") (pinfunction "7_7") (pintype "passive"))
      (node (ref "R83") (pin "1") (pinfunction "1_1") (pintype "passive"))
    )
    (net (code "55") (name "Net-(P4-Pad8)") (class "Default")
      (node (ref "P4") (pin "8") (pinfunction "8_8") (pintype "passive"))
      (node (ref "R84") (pin "1") (pinfunction "1_1") (pintype "passive"))
    )
    (net (code "56") (name "Net-(P4-Pad9)") (class "Default")
      (node (ref "P4") (pin "9") (pinfunction "9_9") (pintype "passive"))
      (node (ref "R85") (pin "1") (pinfunction "1_1") (pintype "passive"))
    )
    (net (code "57") (name "Net-(P4-Pad10)") (class "Default")
      (node (ref "P4") (pin "10") (pinfunction "10_10") (pintype "passive"))
      (node (ref "R95") (pin "1") (pinfunction "1_1") (pintype "passive"))
    )
    (net (code "58") (name "Net-(P4-Pad11)") (class "Default")
      (node (ref "P4") (pin "11") (pinfunction "11_11") (pintype "passive"))
      (node (ref "R96") (pin "1") (pinfunction "1_1") (pintype "passive"))
    )
    (net (code "59") (name "Net-(P4-Pad12)") (class "Default")
      (node (ref "P4") (pin "12") (pinfunction "12_12") (pintype "passive"))
      (node (ref "R97") (pin "1") (pinfunction "1_1") (pintype "passive"))
    )
    (net (code "60") (name "Net-(P5-Pad2)") (class "Default")
      (node (ref "P5") (pin "2") (pinfunction "2_2") (pintype "passive"))
      (node (ref "R41") (pin "2") (pinfunction "2_2") (pintype "passive"))
    )
    (net (code "61") (name "Net-(P5-Pad4)") (class "Default")
      (node (ref "P5") (pin "4") (pinfunction "4_4") (pintype "passive"))
      (node (ref "R42") (pin "2") (pinfunction "2_2") (pintype "passive"))
    )
    (net (code "62") (name "Net-(P5-Pad6)") (class "Default")
      (node (ref "P5") (pin "6") (pinfunction "6_6") (pintype "passive"))
      (node (ref "R92") (pin "2") (pinfunction "2_2") (pintype "passive"))
    )
    (net (code "63") (name "Net-(P5-Pad8)") (class "Default")
      (node (ref "P5") (pin "8") (pinfunction "8_8") (pintype "passive"))
      (node (ref "R99") (pin "2") (pinfunction "2_2") (pintype "passive"))
    )
    (net (code "64") (name "Net-(P6-Pad2)") (class "Default")
      (node (ref "P6") (pin "2") (pinfunction "2_2") (pintype "passive"))
      (node (ref "R17") (pin "2") (pinfunction "2_2") (pintype "passive"))
    )
    (net (code "65") (name "Net-(P6-Pad4)") (class "Default")
      (node (ref "P6") (pin "4") (pinfunction "4_4") (pintype "passive"))
      (node (ref "R18") (pin "2") (pinfunction "2_2") (pintype "passive"))
    )
    (net (code "66") (name "Net-(P6-Pad6)") (class "Default")
      (node (ref "P6") (pin "6") (pinfunction "6_6") (pintype "passive"))
      (node (ref "R19") (pin "2") (pinfunction "2_2") (pintype "passive"))
    )
    (net (code "67") (name "Net-(P6-Pad8)") (class "Default")
      (node (ref "P6") (pin "8") (pinfunction "8_8") (pintype "passive"))
      (node (ref "R20") (pin "2") (pinfunction "2_2") (pintype "passive"))
    )
    (net (code "68") (name "Net-(P6-Pad10)") (class "Default")
      (node (ref "P6") (pin "10") (pinfunction "10_10") (pintype "passive"))
      (node (ref "R21") (pin "2") (pinfunction "2_2") (pintype "passive"))
    )
    (net (code "69") (name "Net-(P6-Pad12)") (class "Default")
      (node (ref "P6") (pin "12") (pinfunction "12_12") (pintype "passive"))
      (node (ref "R22") (pin "2") (pinfunction "2_2") (pintype "passive"))
    )
    (net (code "70") (name "Net-(P6-Pad14)") (class "Default")
      (node (ref "P6") (pin "14") (pinfunction "14_14") (pintype "passive"))
      (node (ref "R23") (pin "2") (pinfunction "2_2") (pintype "passive"))
    )
    (net (code "71") (name "Net-(P6-Pad16)") (class "Default")
      (node (ref "P6") (pin "16") (pinfunction "16_16") (pintype "passive"))
      (node (ref "R24") (pin "2") (pinfunction "2_2") (pintype "passive"))
    )
    (net (code "72") (name "Net-(P6-Pad18)") (class "Default")
      (node (ref "P6") (pin "18") (pinfunction "18_18") (pintype "passive"))
      (node (ref "R25") (pin "2") (pinfunction "2_2") (pintype "passive"))
    )
    (net (code "73") (name "Net-(P6-Pad20)") (class "Default")
      (node (ref "P6") (pin "20") (pinfunction "20_20") (pintype "passive"))
      (node (ref "R26") (pin "2") (pinfunction "2_2") (pintype "passive"))
    )
    (net (code "74") (name "Net-(P6-Pad22)") (class "Default")
      (node (ref "P6") (pin "22") (pinfunction "22_22") (pintype "passive"))
      (node (ref "R27") (pin "2") (pinfunction "2_2") (pintype "passive"))
    )
    (net (code "75") (name "Net-(P6-Pad24)") (class "Default")
      (node (ref "P6") (pin "24") (pinfunction "24_24") (pintype "passive"))
      (node (ref "R28") (pin "2") (pinfunction "2_2") (pintype "passive"))
    )
    (net (code "76") (name "Net-(P6-Pad26)") (class "Default")
      (node (ref "P6") (pin "26") (pinfunction "26_26") (pintype "passive"))
      (node (ref "R29") (pin "2") (pinfunction "2_2") (pintype "passive"))
    )
    (net (code "77") (name "Net-(P6-Pad28)") (class "Default")
      (node (ref "P6") (pin "28") (pinfunction "28_28") (pintype "passive"))
      (node (ref "R30") (pin "2") (pinfunction "2_2") (pintype "passive"))
    )
    (net (code "78") (name "Net-(P6-Pad30)") (class "Default")
      (node (ref "P6") (pin "30") (pinfunction "30_30") (pintype "passive"))
      (node (ref "R31") (pin "2") (pinfunction "2_2") (pintype "passive"))
    )
    (net (code "79") (name "Net-(P6-Pad32)") (class "Default")
      (node (ref "P6") (pin "32") (pinfunction "32_32") (pintype "passive"))
      (node (ref "R32") (pin "2") (pinfunction "2_2") (pintype "passive"))
    )
    (net (code "80") (name "Net-(P6-Pad34)") (class "Default")
      (node (ref "P6") (pin "34") (pinfunction "34_34") (pintype "passive"))
      (node (ref "R33") (pin "2") (pinfunction "2_2") (pintype "passive"))
    )
    (net (code "81") (name "Net-(P6-Pad36)") (class "Default")
      (node (ref "P6") (pin "36") (pinfunction "36_36") (pintype "passive"))
      (node (ref "R34") (pin "2") (pinfunction "2_2") (pintype "passive"))
    )
    (net (code "82") (name "Net-(P6-Pad38)") (class "Default")
      (node (ref "P6") (pin "38") (pinfunction "38_38") (pintype "passive"))
      (node (ref "R35") (pin "2") (pinfunction "2_2") (pintype "passive"))
    )
    (net (code "83") (name "Net-(P6-Pad40)") (class "Default")
      (node (ref "P6") (pin "40") (pinfunction "40_40") (pintype "passive"))
      (node (ref "R36") (pin "2") (pinfunction "2_2") (pintype "passive"))
    )
    (net (code "84") (name "Net-(P6-Pad42)") (class "Default")
      (node (ref "P6") (pin "42") (pinfunction "42_42") (pintype "passive"))
      (node (ref "R37") (pin "2") (pinfunction "2_2") (pintype "passive"))
    )
    (net (code "85") (name "Net-(P6-Pad44)") (class "Default")
      (node (ref "P6") (pin "44") (pinfunction "44_44") (pintype "passive"))
      (node (ref "R38") (pin "2") (pinfunction "2_2") (pintype "passive"))
    )
    (net (code "86") (name "Net-(P6-Pad46)") (class "Default")
      (node (ref "P6") (pin "46") (pinfunction "46_46") (pintype "passive"))
      (node (ref "R39") (pin "2") (pinfunction "2_2") (pintype "passive"))
    )
    (net (code "87") (name "Net-(P6-Pad48)") (class "Default")
      (node (ref "P6") (pin "48") (pinfunction "48_48") (pintype "passive"))
      (node (ref "R40") (pin "2") (pinfunction "2_2") (pintype "passive"))
    )
    (net (code "88") (name "Net-(P7-Pad2)") (class "Default")
      (node (ref "P7") (pin "2") (pinfunction "2_2") (pintype "passive"))
      (node (ref "R100") (pin "2") (pinfunction "2_2") (pintype "passive"))
    )
    (net (code "89") (name "Net-(P7-Pad4)") (class "Default")
      (node (ref "P7") (pin "4") (pinfunction "4_4") (pintype "passive"))
      (node (ref "R101") (pin "2") (pinfunction "2_2") (pintype "passive"))
    )
    (net (code "90") (name "Net-(P7-Pad6)") (class "Default")
      (node (ref "P7") (pin "6") (pinfunction "6_6") (pintype "passive"))
      (node (ref "R102") (pin "2") (pinfunction "2_2") (pintype "passive"))
    )
    (net (code "91") (name "Net-(P15-Pad2)") (class "Default")
      (node (ref "P15") (pin "2") (pinfunction "2_2") (pintype "passive"))
      (node (ref "R73") (pin "2") (pinfunction "2_2") (pintype "passive"))
    )
    (net (code "92") (name "Net-(P15-Pad4)") (class "Default")
      (node (ref "P15") (pin "4") (pinfunction "4_4") (pintype "passive"))
      (node (ref "R74") (pin "2") (pinfunction "2_2") (pintype "passive"))
    )
    (net (code "93") (name "Net-(P15-Pad6)") (class "Default")
      (node (ref "P15") (pin "6") (pinfunction "6_6") (pintype "passive"))
      (node (ref "R75") (pin "2") (pinfunction "2_2") (pintype "passive"))
    )
    (net (code "94") (name "Net-(P15-Pad8)") (class "Default")
      (node (ref "P15") (pin "8") (pinfunction "8_8") (pintype "passive"))
      (node (ref "R76") (pin "2") (pinfunction "2_2") (pintype "passive"))
    )
    (net (code "95") (name "Net-(U1B-CIN)") (class "Default")
      (node (ref "R92") (pin "1") (pinfunction "1_1") (pintype "passive"))
      (node (ref "U1") (pin "G1") (pinfunction "CIN_G1") (pintype "passive"))
    )
    (net (code "96") (name "Net-(U1B-COUT)") (class "Default")
      (node (ref "R99") (pin "1") (pinfunction "1_1") (pintype "passive"))
      (node (ref "U1") (pin "G2") (pinfunction "COUT_G2") (pintype "passive"))
    )
    (net (code "97") (name "Net-(U1B-DIN)") (class "Default")
      (node (ref "R41") (pin "1") (pinfunction "1_1") (pintype "passive"))
      (node (ref "U1") (pin "E2") (pinfunction "DIN_E2") (pintype "passive"))
    )
    (net (code "98") (name "Net-(U1B-DOUT)") (class "Default")
      (node (ref "R42") (pin "1") (pinfunction "1_1") (pintype "passive"))
      (node (ref "U1") (pin "F1") (pinfunction "DOUT_F1") (pintype "passive"))
    )
    (net (code "99") (name "Net-(U1C-SPI_CLKOUT)") (class "Default")
      (node (ref "R74") (pin "1") (pinfunction "1_1") (pintype "passive"))
      (node (ref "U1") (pin "K1") (pinfunction "SPI_CLKOUT_K1") (pintype "passive"))
    )
    (net (code "100") (name "Net-(U1C-SPI_FSSOUT)") (class "Default")
      (node (ref "R75") (pin "1") (pinfunction "1_1") (pintype "passive"))
      (node (ref "U1") (pin "J2") (pinfunction "SPI_FSSOUT_J2") (pintype "passive"))
    )
    (net (code "101") (name "Net-(U1C-SPI_RXD)") (class "Default")
      (node (ref "R76") (pin "1") (pinfunction "1_1") (pintype "passive"))
      (node (ref "U1") (pin "J1") (pinfunction "SPI_RXD_J1") (pintype "passive"))
    )
    (net (code "102") (name "Net-(U1C-SPI_TXD)") (class "Default")
      (node (ref "R73") (pin "1") (pinfunction "1_1") (pintype "passive"))
      (node (ref "U1") (pin "J3") (pinfunction "SPI_TXD_J3") (pintype "passive"))
    )
    (net (code "103") (name "Net-(U1D-GPIO_0)") (class "Default")
      (node (ref "R17") (pin "1") (pinfunction "1_1") (pintype "passive"))
      (node (ref "U1") (pin "B2") (pinfunction "GPIO_0_B2") (pintype "passive"))
    )
    (net (code "104") (name "Net-(U1D-GPIO_1)") (class "Default")
      (node (ref "R18") (pin "1") (pinfunction "1_1") (pintype "passive"))
      (node (ref "U1") (pin "K2") (pinfunction "GPIO_1_K2") (pintype "passive"))
    )
    (net (code "105") (name "Net-(U1D-GPIO_2)") (class "Default")
      (node (ref "R19") (pin "1") (pinfunction "1_1") (pintype "passive"))
      (node (ref "U1") (pin "A2") (pinfunction "GPIO_2_A2") (pintype "passive"))
    )
    (net (code "106") (name "Net-(U1D-GPIO_3)") (class "Default")
      (node (ref "R20") (pin "1") (pinfunction "1_1") (pintype "passive"))
      (node (ref "U1") (pin "K3") (pinfunction "GPIO_3_K3") (pintype "passive"))
    )
    (net (code "107") (name "Net-(U1D-GPIO_4)") (class "Default")
      (node (ref "R21") (pin "1") (pinfunction "1_1") (pintype "passive"))
      (node (ref "U1") (pin "B3") (pinfunction "GPIO_4_B3") (pintype "passive"))
    )
    (net (code "108") (name "Net-(U1D-GPIO_5)") (class "Default")
      (node (ref "R22") (pin "1") (pinfunction "1_1") (pintype "passive"))
      (node (ref "U1") (pin "J4") (pinfunction "GPIO_5_J4") (pintype "passive"))
    )
    (net (code "109") (name "Net-(U1D-GPIO_6)") (class "Default")
      (node (ref "R23") (pin "1") (pinfunction "1_1") (pintype "passive"))
      (node (ref "U1") (pin "A3") (pinfunction "GPIO_6_A3") (pintype "passive"))
    )
    (net (code "110") (name "Net-(U1D-GPIO_7)") (class "Default")
      (node (ref "R24") (pin "1") (pinfunction "1_1") (pintype "passive"))
      (node (ref "U1") (pin "K4") (pinfunction "GPIO_7_K4") (pintype "passive"))
    )
    (net (code "111") (name "Net-(U1D-GPIO_8)") (class "Default")
      (node (ref "R25") (pin "1") (pinfunction "1_1") (pintype "passive"))
      (node (ref "U1") (pin "B4") (pinfunction "GPIO_8_B4") (pintype "passive"))
    )
    (net (code "112") (name "Net-(U1D-GPIO_9)") (class "Default")
      (node (ref "R26") (pin "1") (pinfunction "1_1") (pintype "passive"))
      (node (ref "U1") (pin "K5") (pinfunction "GPIO_9_K5") (pintype "passive"))
    )
    (net (code "113") (name "Net-(U1D-GPIO_10)") (class "Default")
      (node (ref "R27") (pin "1") (pinfunction "1_1") (pintype "passive"))
      (node (ref "U1") (pin "A4") (pinfunction "GPIO_10_A4") (pintype "passive"))
    )
    (net (code "114") (name "Net-(U1D-GPIO_11)") (class "Default")
      (node (ref "R28") (pin "1") (pinfunction "1_1") (pintype "passive"))
      (node (ref "U1") (pin "J5") (pinfunction "GPIO_11_J5") (pintype "passive"))
    )
    (net (code "115") (name "Net-(U1D-GPIO_12)") (class "Default")
      (node (ref "R29") (pin "1") (pinfunction "1_1") (pintype "passive"))
      (node (ref "U1") (pin "B5") (pinfunction "GPIO_12_B5") (pintype "passive"))
    )
    (net (code "116") (name "Net-(U1D-GPIO_13)") (class "Default")
      (node (ref "R30") (pin "1") (pinfunction "1_1") (pintype "passive"))
      (node (ref "U1") (pin "K6") (pinfunction "GPIO_13_K6") (pintype "passive"))
    )
    (net (code "117") (name "Net-(U1D-GPIO_14)") (class "Default")
      (node (ref "R31") (pin "1") (pinfunction "1_1") (pintype "passive"))
      (node (ref "U1") (pin "A5") (pinfunction "GPIO_14_A5") (pintype "passive"))
    )
    (net (code "118") (name "Net-(U1D-GPIO_15)") (class "Default")
      (node (ref "R32") (pin "1") (pinfunction "1_1") (pintype "passive"))
      (node (ref "U1") (pin "J6") (pinfunction "GPIO_15_J6") (pintype "passive"))
    )
    (net (code "119") (name "Net-(U1D-GPIO_16)") (class "Default")
      (node (ref "R33") (pin "1") (pinfunction "1_1") (pintype "passive"))
      (node (ref "U1") (pin "B6") (pinfunction "GPIO_16_B6") (pintype "passive"))
    )
    (net (code "120") (name "Net-(U1D-GPIO_17)") (class "Default")
      (node (ref "R34") (pin "1") (pinfunction "1_1") (pintype "passive"))
      (node (ref "U1") (pin "K7") (pinfunction "GPIO_17_K7") (pintype "passive"))
    )
    (net (code "121") (name "Net-(U1D-GPIO_18)") (class "Default")
      (node (ref "R35") (pin "1") (pinfunction "1_1") (pintype "passive"))
      (node (ref "U1") (pin "A6") (pinfunction "GPIO_18_A6") (pintype "passive"))
    )
    (net (code "122") (name "Net-(U1D-GPIO_19)") (class "Default")
      (node (ref "R36") (pin "1") (pinfunction "1_1") (pintype "passive"))
      (node (ref "U1") (pin "J7") (pinfunction "GPIO_19_J7") (pintype "passive"))
    )
    (net (code "123") (name "Net-(U1D-GPIO_20)") (class "Default")
      (node (ref "R37") (pin "1") (pinfunction "1_1") (pintype "passive"))
      (node (ref "U1") (pin "A7") (pinfunction "GPIO_20_A7") (pintype "passive"))
    )
    (net (code "124") (name "Net-(U1D-GPIO_21)") (class "Default")
      (node (ref "R38") (pin "1") (pinfunction "1_1") (pintype "passive"))
      (node (ref "U1") (pin "K8") (pinfunction "GPIO_21_K8") (pintype "passive"))
    )
    (net (code "125") (name "Net-(U1D-GPIO_22)") (class "Default")
      (node (ref "R39") (pin "1") (pinfunction "1_1") (pintype "passive"))
      (node (ref "U1") (pin "B7") (pinfunction "GPIO_22_B7") (pintype "passive"))
    )
    (net (code "126") (name "Net-(U1D-GPIO_23)") (class "Default")
      (node (ref "R40") (pin "1") (pinfunction "1_1") (pintype "passive"))
      (node (ref "U1") (pin "J8") (pinfunction "GPIO_23_J8") (pintype "passive"))
    )
    (net (code "127") (name "Net-(U1E-ECI)") (class "Default")
      (node (ref "R101") (pin "1") (pinfunction "1_1") (pintype "passive"))
      (node (ref "U1") (pin "H1") (pinfunction "ECI_H1") (pintype "passive"))
    )
    (net (code "128") (name "Net-(U1E-EDI)") (class "Default")
      (node (ref "R102") (pin "1") (pinfunction "1_1") (pintype "passive"))
      (node (ref "U1") (pin "H2") (pinfunction "EDI_H2") (pintype "passive"))
    )
    (net (code "129") (name "Net-(U1E-EMO)") (class "Default")
      (node (ref "R100") (pin "1") (pinfunction "1_1") (pintype "passive"))
      (node (ref "U1") (pin "B1") (pinfunction "EMO_B1") (pintype "passive"))
    )
    (net (code "130") (name "VCC_1P2") (class "Default")
      (node (ref "C54") (pin "2") (pinfunction "2_2") (pintype "passive"))
      (node (ref "U5") (pin "8") (pinfunction "VCC_8") (pintype "passive"))
    )
    (net (code "131") (name "VCC_M3_0P6") (class "Default")
      (node (ref "P2") (pin "3") (pinfunction "3_3") (pintype "passive"))
    )
    (net (code "132") (name "VCC_M3_1P2") (class "Default")
      (node (ref "C31") (pin "2") (pinfunction "2_2") (pintype "passive"))
      (node (ref "C55") (pin "2") (pinfunction "2_2") (pintype "passive"))
      (node (ref "P2") (pin "5") (pinfunction "5_5") (pintype "passive"))
      (node (ref "U2") (pin "8") (pinfunction "VCC_8") (pintype "passive"))
      (node (ref "U6") (pin "8") (pinfunction "VCC_8") (pintype "passive"))
    )
    (net (code "133") (name "VCC_M3_VBATT") (class "Default")
      (node (ref "P2") (pin "7") (pinfunction "7_7") (pintype "passive"))
    )
    (net (code "134") (name "VCC_SOL") (class "Default")
      (node (ref "P2") (pin "1") (pinfunction "1_1") (pintype "passive"))
    )
    (net (code "135") (name "unconnected-(R97-Pad2)") (class "Default")
      (node (ref "R97") (pin "2") (pinfunction "2_2") (pintype "passive"))
    )
    (net (code "136") (name "unconnected-(U2-3Y-Pad2)") (class "Default")
      (node (ref "U2") (pin "2") (pinfunction "3Y_2") (pintype "passive"))
    )
    (net (code "137") (name "unconnected-(U5-3Y-Pad2)") (class "Default")
      (node (ref "U5") (pin "2") (pinfunction "3Y_2") (pintype "passive"))
    )
  )
)
